# atmega128.net
KiCad netlist of a schematic drawn in EAGLE
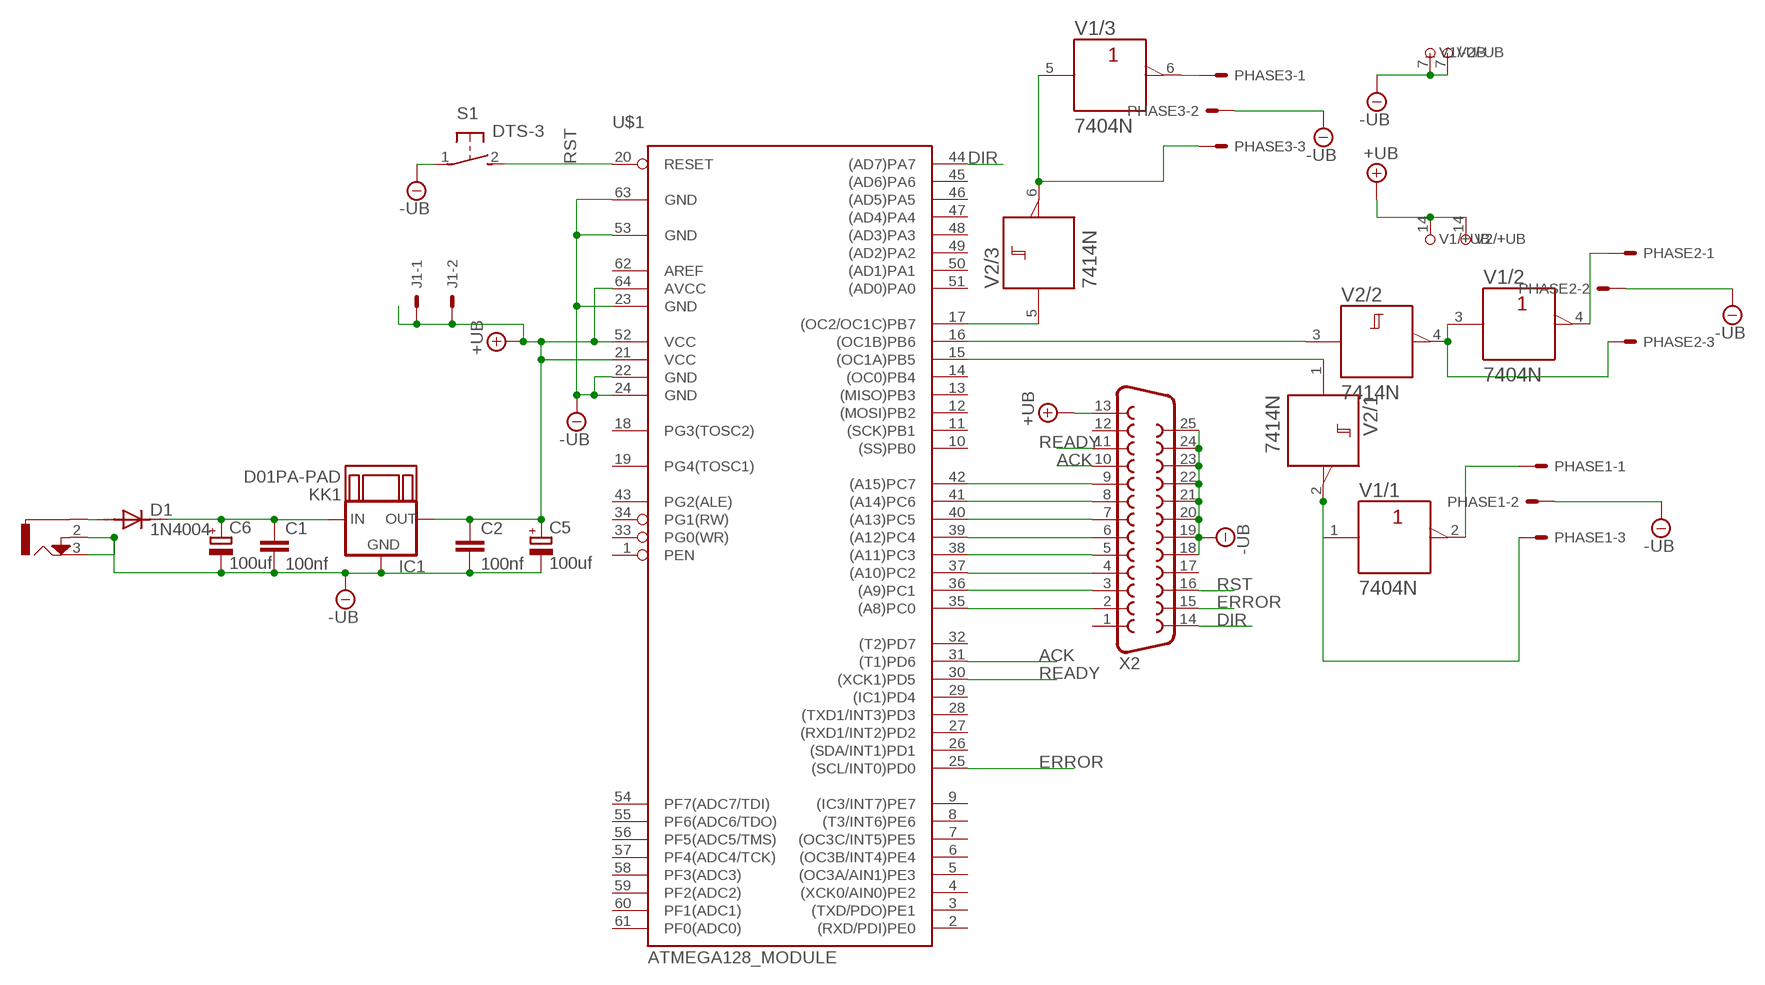
[diagram p0: schematic, sheet 1]

(export (version "E")
  (design (tool "Eeschema 10.0.6"))
  (components
    (comp (ref "C1")
      (value "100nf")
      (footprint "eagle-import:C025-025X050")
      (libsource (lib "eagle-import") (part "C-EU025-025X050"))
    )
    (comp (ref "C2")
      (value "100nf")
      (footprint "eagle-import:C025-025X050")
      (libsource (lib "eagle-import") (part "C-EU025-025X050"))
    )
    (comp (ref "C5")
      (value "100uf")
      (footprint "eagle-import:E2,5-6")
      (libsource (lib "eagle-import") (part "CPOL-EUE2.5-6"))
    )
    (comp (ref "C6")
      (value "100uf")
      (footprint "eagle-import:E2,5-6")
      (libsource (lib "eagle-import") (part "CPOL-EUE2.5-6"))
    )
    (comp (ref "D1")
      (value "1N4004")
      (footprint "eagle-import:DO41-10")
      (libsource (lib "eagle-import") (part "1N4004"))
    )
    (comp (ref "IC1")
      (value "78XXS")
      (footprint "eagle-import:78XXS")
      (libsource (lib "eagle-import") (part "78XXS"))
    )
    (comp (ref "J1")
      (value "22-27-2021-02")
      (footprint "eagle-import:6410-02")
      (libsource (lib "eagle-import") (part "22-?-0227-2021"))
    )
    (comp (ref "KK1")
      (value "D01PA-PAD")
      (footprint "eagle-import:D01PA-PAD")
      (libsource (lib "eagle-import") (part "D01PA-PAD"))
    )
    (comp (ref "PHASE1")
      (value "22-27-2031-03")
      (footprint "eagle-import:6410-03")
      (libsource (lib "eagle-import") (part "22-?-0327-2031"))
    )
    (comp (ref "PHASE2")
      (value "22-27-2031-03")
      (footprint "eagle-import:6410-03")
      (libsource (lib "eagle-import") (part "22-?-0327-2031"))
    )
    (comp (ref "PHASE3")
      (value "22-27-2031-03")
      (footprint "eagle-import:6410-03")
      (libsource (lib "eagle-import") (part "22-?-0327-2031"))
    )
    (comp (ref "S1")
      (value "DTS-3")
      (footprint "eagle-import:DTS-3")
      (libsource (lib "eagle-import") (part "DTS-3"))
    )
    (comp (ref "U$1")
      (value "ATMEGA128_MODULE")
      (footprint "eagle-import:ATMEGA128_MODULE")
      (libsource (lib "eagle-import") (part "ATMEGA128_MODULE"))
    )
    (comp (ref "U$2")
      (value "DC-21MM")
      (footprint "eagle-import:DC-21MM")
      (libsource (lib "eagle-import") (part "DC-21MM"))
    )
    (comp (ref "V1")
      (value "7404N")
      (footprint "eagle-import:DIL14")
      (libsource (lib "eagle-import") (part "7404N"))
    )
    (comp (ref "V2")
      (value "7414N")
      (footprint "eagle-import:DIL14")
      (libsource (lib "eagle-import") (part "7414N"))
    )
    (comp (ref "X2")
      (value "F25HP")
      (footprint "eagle-import:F25HP")
      (libsource (lib "eagle-import") (part "F25HP"))
    )
  )
  (nets
    (net (code "1") (name "+UB") (class "Default")
      (node (ref "C2") (pin "1") (pinfunction "1_1") (pintype "passive"))
      (node (ref "C5") (pin "+") (pinfunction "+_+") (pintype "passive"))
      (node (ref "IC1") (pin "OUT") (pinfunction "OUT_OUT") (pintype "passive"))
      (node (ref "J1") (pin "1") (pinfunction "S_1") (pintype "passive"))
      (node (ref "J1") (pin "2") (pinfunction "S_2") (pintype "passive"))
      (node (ref "U$1") (pin "21") (pinfunction "VCC_21") (pintype "power_in"))
      (node (ref "U$1") (pin "52") (pinfunction "VCC_52") (pintype "power_in"))
      (node (ref "U$1") (pin "64") (pinfunction "AVCC_64") (pintype "power_in"))
      (node (ref "V1") (pin "14") (pinfunction "+UB_14") (pintype "power_in"))
      (node (ref "V2") (pin "14") (pinfunction "+UB_14") (pintype "power_in"))
      (node (ref "X2") (pin "13") (pinfunction "13_13") (pintype "passive"))
    )
    (net (code "2") (name "-UB") (class "Default")
      (node (ref "C1") (pin "2") (pinfunction "2_2") (pintype "passive"))
      (node (ref "C2") (pin "2") (pinfunction "2_2") (pintype "passive"))
      (node (ref "C5") (pin "-") (pinfunction "-_-") (pintype "passive"))
      (node (ref "C6") (pin "-") (pinfunction "-_-") (pintype "passive"))
      (node (ref "IC1") (pin "GND") (pinfunction "GND_GND") (pintype "input"))
      (node (ref "PHASE1") (pin "2") (pinfunction "S_2") (pintype "passive"))
      (node (ref "PHASE2") (pin "2") (pinfunction "S_2") (pintype "passive"))
      (node (ref "PHASE3") (pin "2") (pinfunction "S_2") (pintype "passive"))
      (node (ref "S1") (pin "1") (pinfunction "1_1") (pintype "passive"))
      (node (ref "U$1") (pin "22") (pinfunction "GND_22") (pintype "power_in"))
      (node (ref "U$1") (pin "23") (pinfunction "GND_23") (pintype "power_in"))
      (node (ref "U$1") (pin "24") (pinfunction "GND_24") (pintype "power_in"))
      (node (ref "U$1") (pin "53") (pinfunction "GND_53") (pintype "power_in"))
      (node (ref "U$1") (pin "63") (pinfunction "GND_63") (pintype "power_in"))
      (node (ref "U$2") (pin "2") (pinfunction "2_2") (pintype "passive"))
      (node (ref "U$2") (pin "3") (pinfunction "3_3") (pintype "passive"))
      (node (ref "V1") (pin "7") (pinfunction "-UB_7") (pintype "power_in"))
      (node (ref "V2") (pin "7") (pinfunction "-UB_7") (pintype "power_in"))
      (node (ref "X2") (pin "18") (pinfunction "18_18") (pintype "passive"))
      (node (ref "X2") (pin "19") (pinfunction "19_19") (pintype "passive"))
      (node (ref "X2") (pin "20") (pinfunction "20_20") (pintype "passive"))
      (node (ref "X2") (pin "21") (pinfunction "21_21") (pintype "passive"))
      (node (ref "X2") (pin "22") (pinfunction "22_22") (pintype "passive"))
      (node (ref "X2") (pin "23") (pinfunction "23_23") (pintype "passive"))
      (node (ref "X2") (pin "24") (pinfunction "24_24") (pintype "passive"))
      (node (ref "X2") (pin "25") (pinfunction "25_25") (pintype "passive"))
    )
    (net (code "3") (name "/ACK") (class "Default")
      (node (ref "U$1") (pin "31") (pinfunction "(T1)PD6_31") (pintype "bidirectional"))
      (node (ref "X2") (pin "10") (pinfunction "10_10") (pintype "passive"))
    )
    (net (code "4") (name "/DIR") (class "Default")
      (node (ref "U$1") (pin "44") (pinfunction "(AD7)PA7_44") (pintype "bidirectional"))
      (node (ref "X2") (pin "14") (pinfunction "14_14") (pintype "passive"))
    )
    (net (code "5") (name "/ERROR") (class "Default")
      (node (ref "U$1") (pin "25") (pinfunction "(SCL/INT0)PD0_25") (pintype "bidirectional"))
      (node (ref "X2") (pin "15") (pinfunction "15_15") (pintype "passive"))
    )
    (net (code "6") (name "/READY") (class "Default")
      (node (ref "U$1") (pin "30") (pinfunction "(XCK1)PD5_30") (pintype "bidirectional"))
      (node (ref "X2") (pin "11") (pinfunction "11_11") (pintype "passive"))
    )
    (net (code "7") (name "/RST") (class "Default")
      (node (ref "S1") (pin "2") (pinfunction "2_2") (pintype "passive"))
      (node (ref "U$1") (pin "20") (pinfunction "RESET_20") (pintype "input"))
      (node (ref "X2") (pin "16") (pinfunction "16_16") (pintype "passive"))
    )
    (net (code "8") (name "Net-(C1-Pad1)") (class "Default")
      (node (ref "C1") (pin "1") (pinfunction "1_1") (pintype "passive"))
      (node (ref "C6") (pin "+") (pinfunction "+_+") (pintype "passive"))
      (node (ref "D1") (pin "C") (pinfunction "C_C") (pintype "passive"))
      (node (ref "IC1") (pin "IN") (pinfunction "IN_IN") (pintype "input"))
    )
    (net (code "9") (name "Net-(D1-PadA)") (class "Default")
      (node (ref "D1") (pin "A") (pinfunction "A_A") (pintype "passive"))
      (node (ref "U$2") (pin "1") (pinfunction "1_1") (pintype "passive"))
    )
    (net (code "10") (name "Net-(PHASE1A-S)") (class "Default")
      (node (ref "PHASE1") (pin "1") (pinfunction "S_1") (pintype "passive"))
      (node (ref "V1") (pin "2") (pinfunction "Y_2") (pintype "output"))
    )
    (net (code "11") (name "Net-(PHASE1C-S)") (class "Default")
      (node (ref "PHASE1") (pin "3") (pinfunction "S_3") (pintype "passive"))
      (node (ref "V1") (pin "1") (pinfunction "A_1") (pintype "input"))
      (node (ref "V2") (pin "2") (pinfunction "Y_2") (pintype "output"))
    )
    (net (code "12") (name "Net-(PHASE2A-S)") (class "Default")
      (node (ref "PHASE2") (pin "1") (pinfunction "S_1") (pintype "passive"))
      (node (ref "V1") (pin "4") (pinfunction "Y_4") (pintype "output"))
    )
    (net (code "13") (name "Net-(PHASE2C-S)") (class "Default")
      (node (ref "PHASE2") (pin "3") (pinfunction "S_3") (pintype "passive"))
      (node (ref "V1") (pin "3") (pinfunction "A_3") (pintype "input"))
      (node (ref "V2") (pin "4") (pinfunction "Y_4") (pintype "output"))
    )
    (net (code "14") (name "Net-(PHASE3A-S)") (class "Default")
      (node (ref "PHASE3") (pin "1") (pinfunction "S_1") (pintype "passive"))
      (node (ref "V1") (pin "6") (pinfunction "Y_6") (pintype "output"))
    )
    (net (code "15") (name "Net-(PHASE3C-S)") (class "Default")
      (node (ref "PHASE3") (pin "3") (pinfunction "S_3") (pintype "passive"))
      (node (ref "V1") (pin "5") (pinfunction "A_5") (pintype "input"))
      (node (ref "V2") (pin "6") (pinfunction "Y_6") (pintype "output"))
    )
    (net (code "16") (name "Net-(U$1-(A8)PC0)") (class "Default")
      (node (ref "U$1") (pin "35") (pinfunction "(A8)PC0_35") (pintype "output"))
      (node (ref "X2") (pin "2") (pinfunction "2_2") (pintype "passive"))
    )
    (net (code "17") (name "Net-(U$1-(A9)PC1)") (class "Default")
      (node (ref "U$1") (pin "36") (pinfunction "(A9)PC1_36") (pintype "output"))
      (node (ref "X2") (pin "3") (pinfunction "3_3") (pintype "passive"))
    )
    (net (code "18") (name "Net-(U$1-(A10)PC2)") (class "Default")
      (node (ref "U$1") (pin "37") (pinfunction "(A10)PC2_37") (pintype "output"))
      (node (ref "X2") (pin "4") (pinfunction "4_4") (pintype "passive"))
    )
    (net (code "19") (name "Net-(U$1-(A11)PC3)") (class "Default")
      (node (ref "U$1") (pin "38") (pinfunction "(A11)PC3_38") (pintype "output"))
      (node (ref "X2") (pin "5") (pinfunction "5_5") (pintype "passive"))
    )
    (net (code "20") (name "Net-(U$1-(A12)PC4)") (class "Default")
      (node (ref "U$1") (pin "39") (pinfunction "(A12)PC4_39") (pintype "output"))
      (node (ref "X2") (pin "6") (pinfunction "6_6") (pintype "passive"))
    )
    (net (code "21") (name "Net-(U$1-(A13)PC5)") (class "Default")
      (node (ref "U$1") (pin "40") (pinfunction "(A13)PC5_40") (pintype "output"))
      (node (ref "X2") (pin "7") (pinfunction "7_7") (pintype "passive"))
    )
    (net (code "22") (name "Net-(U$1-(A14)PC6)") (class "Default")
      (node (ref "U$1") (pin "41") (pinfunction "(A14)PC6_41") (pintype "output"))
      (node (ref "X2") (pin "8") (pinfunction "8_8") (pintype "passive"))
    )
    (net (code "23") (name "Net-(U$1-(A15)PC7)") (class "Default")
      (node (ref "U$1") (pin "42") (pinfunction "(A15)PC7_42") (pintype "output"))
      (node (ref "X2") (pin "9") (pinfunction "9_9") (pintype "passive"))
    )
    (net (code "24") (name "Net-(U$1-(OC1A)PB5)") (class "Default")
      (node (ref "U$1") (pin "15") (pinfunction "(OC1A)PB5_15") (pintype "bidirectional"))
      (node (ref "V2") (pin "1") (pinfunction "A_1") (pintype "input"))
    )
    (net (code "25") (name "Net-(U$1-(OC1B)PB6)") (class "Default")
      (node (ref "U$1") (pin "16") (pinfunction "(OC1B)PB6_16") (pintype "bidirectional"))
      (node (ref "V2") (pin "3") (pinfunction "A_3") (pintype "input"))
    )
    (net (code "26") (name "Net-(U$1-(OC2{slash}OC1C)PB7)") (class "Default")
      (node (ref "U$1") (pin "17") (pinfunction "(OC2/OC1C)PB7_17") (pintype "bidirectional"))
      (node (ref "V2") (pin "5") (pinfunction "A_5") (pintype "input"))
    )
    (net (code "27") (name "unconnected-(U$1-(AD0)PA0-Pad51)") (class "Default")
      (node (ref "U$1") (pin "51") (pinfunction "(AD0)PA0_51") (pintype "bidirectional"))
    )
    (net (code "28") (name "unconnected-(U$1-(AD1)PA1-Pad50)") (class "Default")
      (node (ref "U$1") (pin "50") (pinfunction "(AD1)PA1_50") (pintype "bidirectional"))
    )
    (net (code "29") (name "unconnected-(U$1-(AD2)PA2-Pad49)") (class "Default")
      (node (ref "U$1") (pin "49") (pinfunction "(AD2)PA2_49") (pintype "bidirectional"))
    )
    (net (code "30") (name "unconnected-(U$1-(AD3)PA3-Pad48)") (class "Default")
      (node (ref "U$1") (pin "48") (pinfunction "(AD3)PA3_48") (pintype "bidirectional"))
    )
    (net (code "31") (name "unconnected-(U$1-(AD4)PA4-Pad47)") (class "Default")
      (node (ref "U$1") (pin "47") (pinfunction "(AD4)PA4_47") (pintype "bidirectional"))
    )
    (net (code "32") (name "unconnected-(U$1-(AD5)PA5-Pad46)") (class "Default")
      (node (ref "U$1") (pin "46") (pinfunction "(AD5)PA5_46") (pintype "bidirectional"))
    )
    (net (code "33") (name "unconnected-(U$1-(AD6)PA6-Pad45)") (class "Default")
      (node (ref "U$1") (pin "45") (pinfunction "(AD6)PA6_45") (pintype "bidirectional"))
    )
    (net (code "34") (name "unconnected-(U$1-(IC1)PD4-Pad29)") (class "Default")
      (node (ref "U$1") (pin "29") (pinfunction "(IC1)PD4_29") (pintype "bidirectional"))
    )
    (net (code "35") (name "unconnected-(U$1-(IC3{slash}INT7)PE7-Pad9)") (class "Default")
      (node (ref "U$1") (pin "9") (pinfunction "(IC3/INT7)PE7_9") (pintype "bidirectional"))
    )
    (net (code "36") (name "unconnected-(U$1-(MISO)PB3-Pad13)") (class "Default")
      (node (ref "U$1") (pin "13") (pinfunction "(MISO)PB3_13") (pintype "bidirectional"))
    )
    (net (code "37") (name "unconnected-(U$1-(MOSI)PB2-Pad12)") (class "Default")
      (node (ref "U$1") (pin "12") (pinfunction "(MOSI)PB2_12") (pintype "bidirectional"))
    )
    (net (code "38") (name "unconnected-(U$1-(OC0)PB4-Pad14)") (class "Default")
      (node (ref "U$1") (pin "14") (pinfunction "(OC0)PB4_14") (pintype "bidirectional"))
    )
    (net (code "39") (name "unconnected-(U$1-(OC3A{slash}AIN1)PE3-Pad5)") (class "Default")
      (node (ref "U$1") (pin "5") (pinfunction "(OC3A/AIN1)PE3_5") (pintype "bidirectional"))
    )
    (net (code "40") (name "unconnected-(U$1-(OC3B{slash}INT4)PE4-Pad6)") (class "Default")
      (node (ref "U$1") (pin "6") (pinfunction "(OC3B/INT4)PE4_6") (pintype "bidirectional"))
    )
    (net (code "41") (name "unconnected-(U$1-(OC3C{slash}INT5)PE5-Pad7)") (class "Default")
      (node (ref "U$1") (pin "7") (pinfunction "(OC3C/INT5)PE5_7") (pintype "bidirectional"))
    )
    (net (code "42") (name "unconnected-(U$1-(RXD1{slash}INT2)PD2-Pad27)") (class "Default")
      (node (ref "U$1") (pin "27") (pinfunction "(RXD1/INT2)PD2_27") (pintype "bidirectional"))
    )
    (net (code "43") (name "unconnected-(U$1-(RXD{slash}PDI)PE0-Pad2)") (class "Default")
      (node (ref "U$1") (pin "2") (pinfunction "(RXD/PDI)PE0_2") (pintype "bidirectional"))
    )
    (net (code "44") (name "unconnected-(U$1-(SCK)PB1-Pad11)") (class "Default")
      (node (ref "U$1") (pin "11") (pinfunction "(SCK)PB1_11") (pintype "bidirectional"))
    )
    (net (code "45") (name "unconnected-(U$1-(SDA{slash}INT1)PD1-Pad26)") (class "Default")
      (node (ref "U$1") (pin "26") (pinfunction "(SDA/INT1)PD1_26") (pintype "bidirectional"))
    )
    (net (code "46") (name "unconnected-(U$1-(SS)PB0-Pad10)") (class "Default")
      (node (ref "U$1") (pin "10") (pinfunction "(SS)PB0_10") (pintype "bidirectional"))
    )
    (net (code "47") (name "unconnected-(U$1-(T2)PD7-Pad32)") (class "Default")
      (node (ref "U$1") (pin "32") (pinfunction "(T2)PD7_32") (pintype "bidirectional"))
    )
    (net (code "48") (name "unconnected-(U$1-(T3{slash}INT6)PE6-Pad8)") (class "Default")
      (node (ref "U$1") (pin "8") (pinfunction "(T3/INT6)PE6_8") (pintype "bidirectional"))
    )
    (net (code "49") (name "unconnected-(U$1-(TXD1{slash}INT3)PD3-Pad28)") (class "Default")
      (node (ref "U$1") (pin "28") (pinfunction "(TXD1/INT3)PD3_28") (pintype "bidirectional"))
    )
    (net (code "50") (name "unconnected-(U$1-(TXD{slash}PDO)PE1-Pad3)") (class "Default")
      (node (ref "U$1") (pin "3") (pinfunction "(TXD/PDO)PE1_3") (pintype "bidirectional"))
    )
    (net (code "51") (name "unconnected-(U$1-(XCK0{slash}AIN0)PE2-Pad4)") (class "Default")
      (node (ref "U$1") (pin "4") (pinfunction "(XCK0/AIN0)PE2_4") (pintype "bidirectional"))
    )
    (net (code "52") (name "unconnected-(U$1-AREF-Pad62)") (class "Default")
      (node (ref "U$1") (pin "62") (pinfunction "AREF_62") (pintype "passive"))
    )
    (net (code "53") (name "unconnected-(U$1-PEN-Pad1)") (class "Default")
      (node (ref "U$1") (pin "1") (pinfunction "PEN_1") (pintype "input"))
    )
    (net (code "54") (name "unconnected-(U$1-PF0(ADC0)-Pad61)") (class "Default")
      (node (ref "U$1") (pin "61") (pinfunction "PF0(ADC0)_61") (pintype "input"))
    )
    (net (code "55") (name "unconnected-(U$1-PF1(ADC1)-Pad60)") (class "Default")
      (node (ref "U$1") (pin "60") (pinfunction "PF1(ADC1)_60") (pintype "input"))
    )
    (net (code "56") (name "unconnected-(U$1-PF2(ADC2)-Pad59)") (class "Default")
      (node (ref "U$1") (pin "59") (pinfunction "PF2(ADC2)_59") (pintype "input"))
    )
    (net (code "57") (name "unconnected-(U$1-PF3(ADC3)-Pad58)") (class "Default")
      (node (ref "U$1") (pin "58") (pinfunction "PF3(ADC3)_58") (pintype "input"))
    )
    (net (code "58") (name "unconnected-(U$1-PF4(ADC4{slash}TCK)-Pad57)") (class "Default")
      (node (ref "U$1") (pin "57") (pinfunction "PF4(ADC4/TCK)_57") (pintype "input"))
    )
    (net (code "59") (name "unconnected-(U$1-PF5(ADC5{slash}TMS)-Pad56)") (class "Default")
      (node (ref "U$1") (pin "56") (pinfunction "PF5(ADC5/TMS)_56") (pintype "input"))
    )
    (net (code "60") (name "unconnected-(U$1-PF6(ADC6{slash}TDO)-Pad55)") (class "Default")
      (node (ref "U$1") (pin "55") (pinfunction "PF6(ADC6/TDO)_55") (pintype "input"))
    )
    (net (code "61") (name "unconnected-(U$1-PF7(ADC7{slash}TDI)-Pad54)") (class "Default")
      (node (ref "U$1") (pin "54") (pinfunction "PF7(ADC7/TDI)_54") (pintype "input"))
    )
    (net (code "62") (name "unconnected-(U$1-PG0(WR)-Pad33)") (class "Default")
      (node (ref "U$1") (pin "33") (pinfunction "PG0(WR)_33") (pintype "bidirectional"))
    )
    (net (code "63") (name "unconnected-(U$1-PG1(RW)-Pad34)") (class "Default")
      (node (ref "U$1") (pin "34") (pinfunction "PG1(RW)_34") (pintype "bidirectional"))
    )
    (net (code "64") (name "unconnected-(U$1-PG2(ALE)-Pad43)") (class "Default")
      (node (ref "U$1") (pin "43") (pinfunction "PG2(ALE)_43") (pintype "bidirectional"))
    )
    (net (code "65") (name "unconnected-(U$1-PG3(TOSC2)-Pad18)") (class "Default")
      (node (ref "U$1") (pin "18") (pinfunction "PG3(TOSC2)_18") (pintype "bidirectional"))
    )
    (net (code "66") (name "unconnected-(U$1-PG4(TOSC1)-Pad19)") (class "Default")
      (node (ref "U$1") (pin "19") (pinfunction "PG4(TOSC1)_19") (pintype "bidirectional"))
    )
    (net (code "67") (name "unconnected-(X2-Pad1)") (class "Default")
      (node (ref "X2") (pin "1") (pinfunction "1_1") (pintype "passive"))
    )
    (net (code "68") (name "unconnected-(X2-Pad12)") (class "Default")
      (node (ref "X2") (pin "12") (pinfunction "12_12") (pintype "passive"))
    )
    (net (code "69") (name "unconnected-(X2-Pad17)") (class "Default")
      (node (ref "X2") (pin "17") (pinfunction "17_17") (pintype "passive"))
    )
  )
)
